# S7CAS-PLEIADES-CARTE-MERE_P01_FPGA-BANK3.net
KiCad netlist of a schematic drawn in Altium Designer
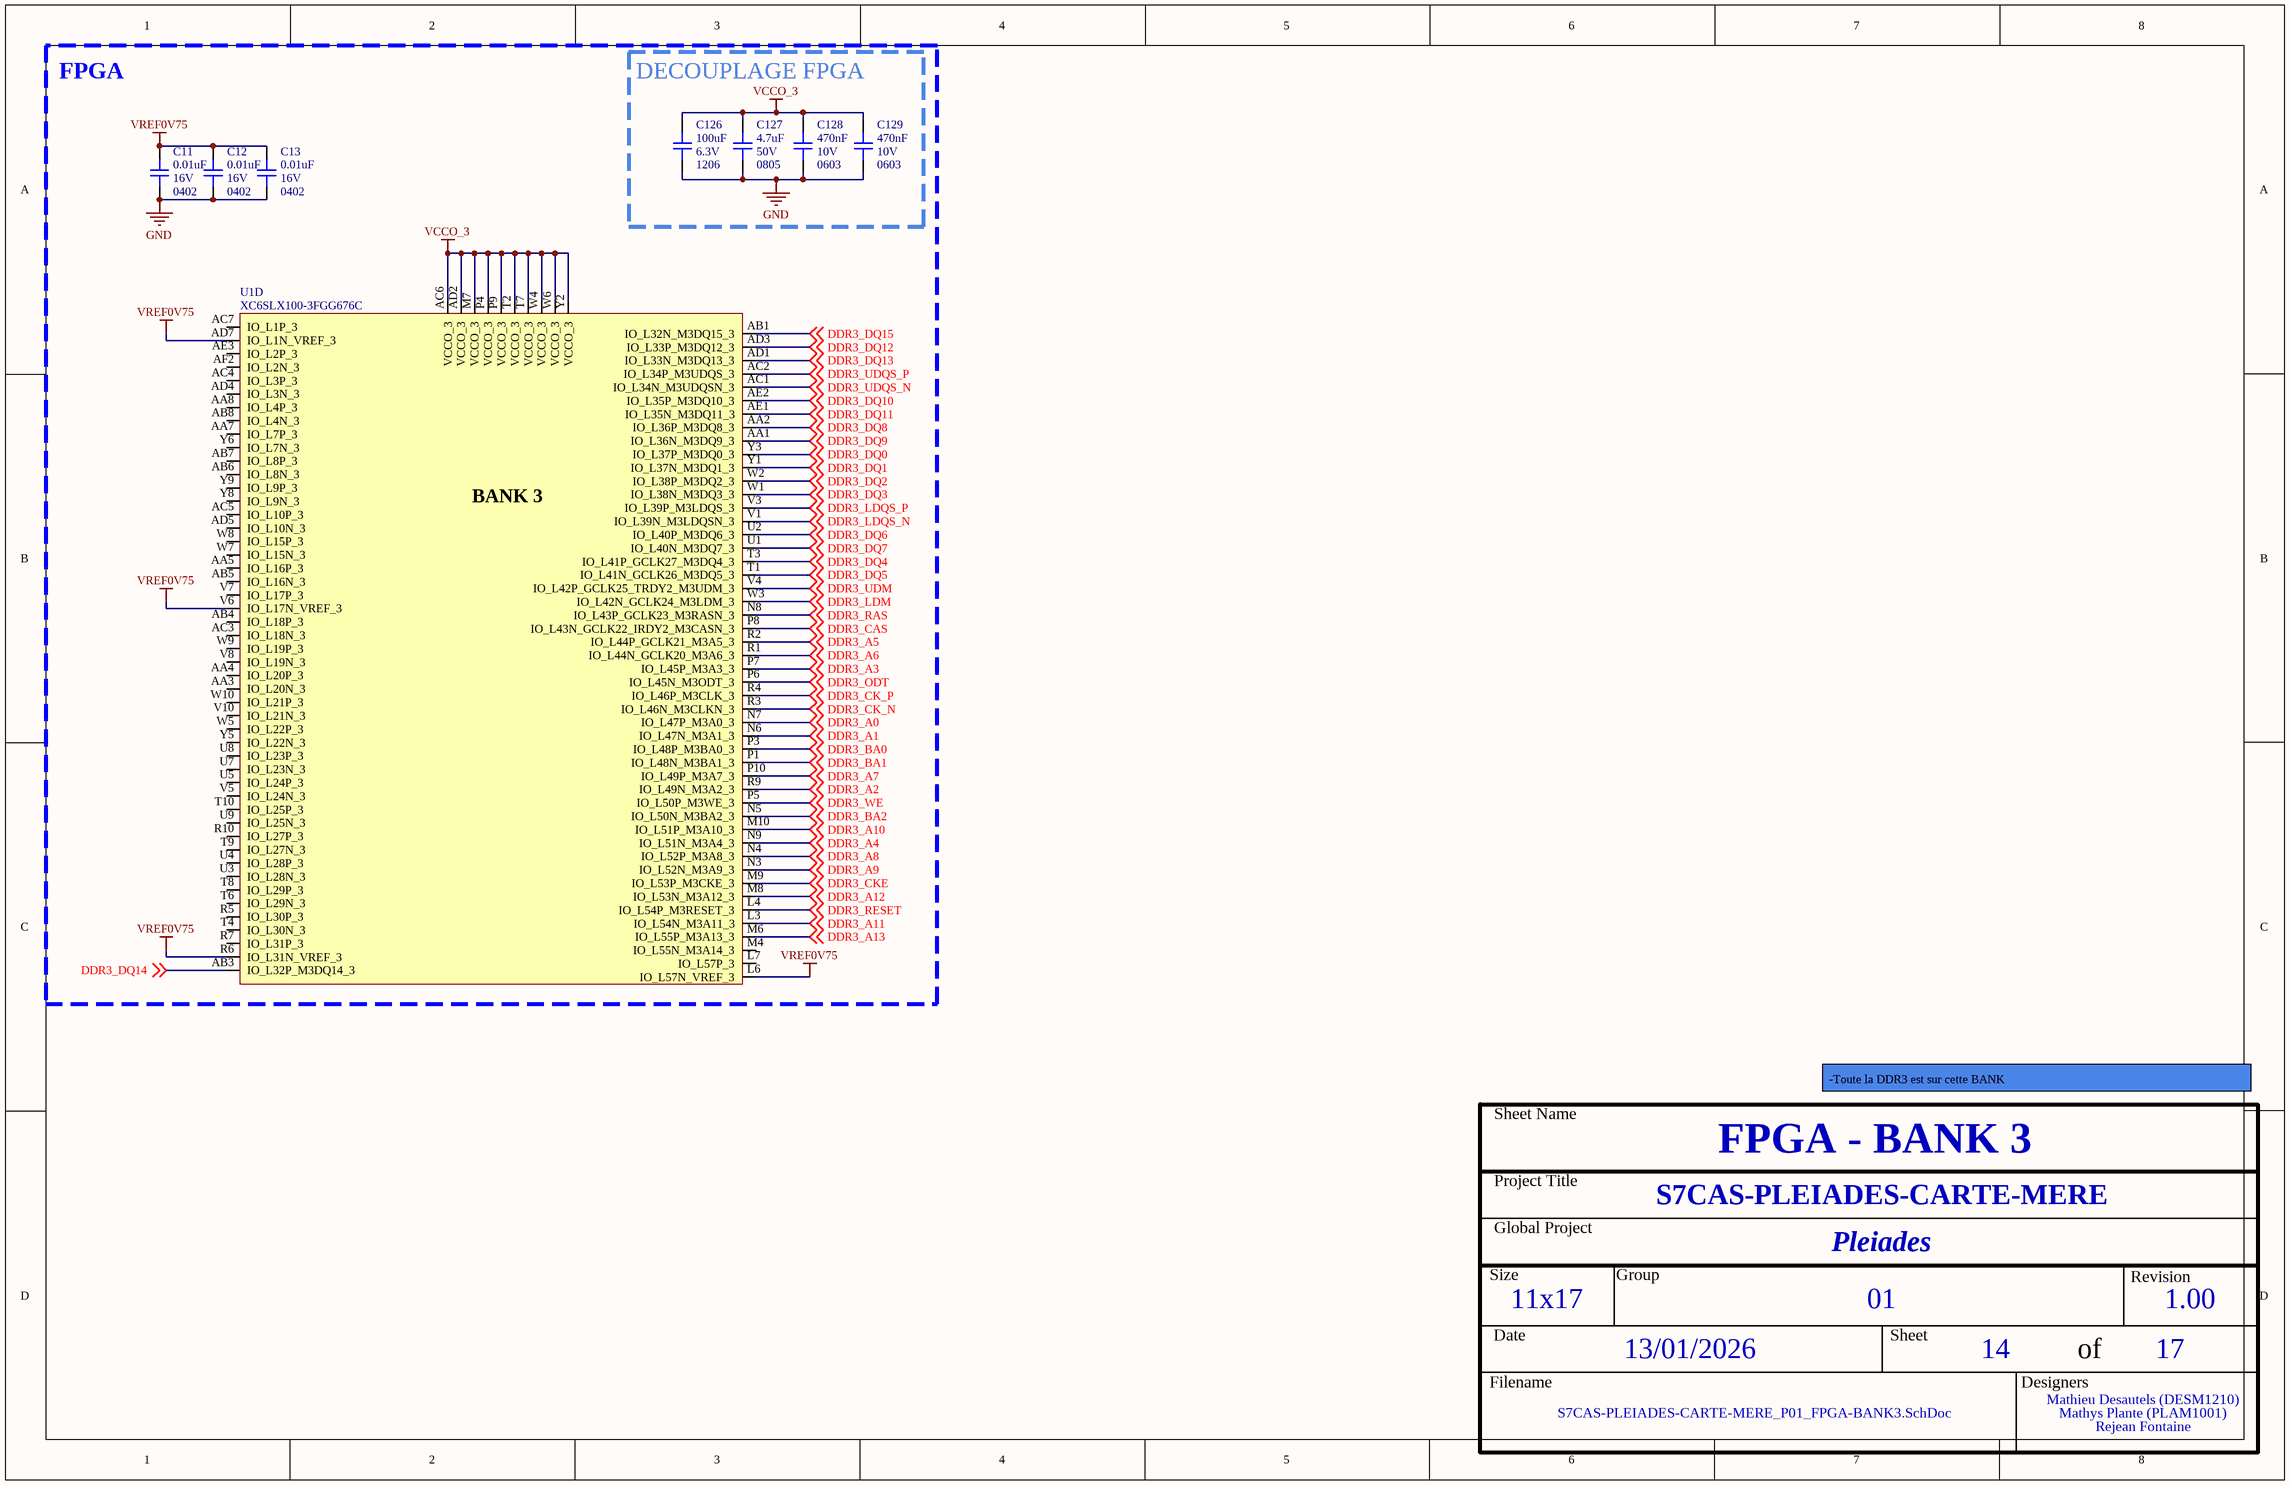
[diagram p0: S7CAS-PLEIADES-CARTE-MERE_P01_FPGA-BANK3.SchDoc]

(export (version "E")
  (design (tool "Eeschema 10.0.6"))
  (components
    (comp (ref "C11")
      (value "0.01uF")
      (footprint "CAP_0402")
      (description "10000 pF ±10% 16V Ceramic Capacitor X7R 0402 (1005 Metric)")
      (fields
        (field (name "MFG") "KEMET")
        (field (name "VOLTAGE") "16V")
        (field (name "PACKAGE") "0402")
        (field (name "MFG PART NUMBER") "C0402C103K4RACTU")
        (field (name "CREATEDBY") "Jonathan Bouchard")
      )
      (libsource (lib "s7cas_lib2023") (part "CAP - 0402"))
    )
    (comp (ref "C12")
      (value "0.01uF")
      (footprint "CAP_0402")
      (description "10000 pF ±10% 16V Ceramic Capacitor X7R 0402 (1005 Metric)")
      (fields
        (field (name "MFG") "KEMET")
        (field (name "VOLTAGE") "16V")
        (field (name "PACKAGE") "0402")
        (field (name "MFG PART NUMBER") "C0402C103K4RACTU")
        (field (name "CREATEDBY") "Jonathan Bouchard")
      )
      (libsource (lib "s7cas_lib2023") (part "CAP - 0402"))
    )
    (comp (ref "C13")
      (value "0.01uF")
      (footprint "CAP_0402")
      (description "10000 pF ±10% 16V Ceramic Capacitor X7R 0402 (1005 Metric)")
      (fields
        (field (name "MFG") "KEMET")
        (field (name "VOLTAGE") "16V")
        (field (name "PACKAGE") "0402")
        (field (name "MFG PART NUMBER") "C0402C103K4RACTU")
        (field (name "CREATEDBY") "Jonathan Bouchard")
      )
      (libsource (lib "s7cas_lib2023") (part "CAP - 0402"))
    )
    (comp (ref "C126")
      (value "100uF")
      (footprint "CAP_1206")
      (description "100 µF ±20% 6.3V Ceramic Capacitor X6T 1206 (3216 Metric)")
      (fields
        (field (name "MFG") "Murata Electronics")
        (field (name "MFG PART NUMBER") "GRM31CD80J107MEA8K")
        (field (name "VOLTAGE") "6.3V")
        (field (name "PACKAGE") "1206")
        (field (name "CREATEDBY") "Jonathan Bouchard")
      )
      (libsource (lib "s7cas_lib2023") (part "CAP - 1206"))
    )
    (comp (ref "C127")
      (value "4.7uF")
      (footprint "CAP_0805")
      (description "4.7 µF ±10% 50V Ceramic Capacitor X5R 0805 (2012 Metric)")
      (fields
        (field (name "MFG") "Murata Electronics")
        (field (name "MFG PART NUMBER") "GRT21BR61H475KE13L")
        (field (name "VOLTAGE") "50V")
        (field (name "PACKAGE") "0805")
        (field (name "CREATEDBY") "Jonathan Bouchard")
      )
      (libsource (lib "s7cas_lib2023") (part "CAP - 0805"))
    )
    (comp (ref "C128")
      (value "470nF")
      (footprint "CAP_0603")
      (description "CAP - 0603")
      (fields
        (field (name "MFG PART NUMBER") "C0603X474K8RAC")
        (field (name "VOLTAGE") "10V")
        (field (name "PACKAGE") "0603")
        (field (name "CREATEDBY") "Jonathan Bouchard")
      )
      (libsource (lib "s7cas_lib2023") (part "CAP - 0603"))
    )
    (comp (ref "C129")
      (value "470nF")
      (footprint "CAP_0603")
      (description "CAP - 0603")
      (fields
        (field (name "MFG PART NUMBER") "C0603X474K8RAC")
        (field (name "VOLTAGE") "10V")
        (field (name "PACKAGE") "0603")
        (field (name "CREATEDBY") "Jonathan Bouchard")
      )
      (libsource (lib "s7cas_lib2023") (part "CAP - 0603"))
    )
    (comp (ref "U1")
      (value "XC6SLX100-3FGG676C")
      (footprint "FPGA_XILINX_FGG676")
      (description "FPGA - XILINX SPARTAN 6 480 I/O - BGA-676")
      (fields
        (field (name "VOLTAGE") "1.14 V ~ 1.26 V")
        (field (name "MFG") "Xilinx")
        (field (name "CREATEDBY") "Jonathan Bouchard")
      )
      (libsource (lib "s7cas_lib2023") (part "FPGA_XC6SLX100-3FGG676C"))
    )
  )
  (nets
    (net (code "1") (name "DDR3_A0") (class "Default")
      (node (ref "U1") (pin "N7") (pinfunction "IO_L47P_M3A0_3_N7") (pintype "passive"))
    )
    (net (code "2") (name "DDR3_A1") (class "Default")
      (node (ref "U1") (pin "N6") (pinfunction "IO_L47N_M3A1_3_N6") (pintype "passive"))
    )
    (net (code "3") (name "DDR3_A2") (class "Default")
      (node (ref "U1") (pin "R9") (pinfunction "IO_L49N_M3A2_3_R9") (pintype "passive"))
    )
    (net (code "4") (name "DDR3_A3") (class "Default")
      (node (ref "U1") (pin "P7") (pinfunction "IO_L45P_M3A3_3_P7") (pintype "passive"))
    )
    (net (code "5") (name "DDR3_A4") (class "Default")
      (node (ref "U1") (pin "N9") (pinfunction "IO_L51N_M3A4_3_N9") (pintype "passive"))
    )
    (net (code "6") (name "DDR3_A5") (class "Default")
      (node (ref "U1") (pin "R2") (pinfunction "IO_L44P_GCLK21_M3A5_3_R2") (pintype "passive"))
    )
    (net (code "7") (name "DDR3_A6") (class "Default")
      (node (ref "U1") (pin "R1") (pinfunction "IO_L44N_GCLK20_M3A6_3_R1") (pintype "passive"))
    )
    (net (code "8") (name "DDR3_A7") (class "Default")
      (node (ref "U1") (pin "P10") (pinfunction "IO_L49P_M3A7_3_P10") (pintype "passive"))
    )
    (net (code "9") (name "DDR3_A8") (class "Default")
      (node (ref "U1") (pin "N4") (pinfunction "IO_L52P_M3A8_3_N4") (pintype "passive"))
    )
    (net (code "10") (name "DDR3_A9") (class "Default")
      (node (ref "U1") (pin "N3") (pinfunction "IO_L52N_M3A9_3_N3") (pintype "passive"))
    )
    (net (code "11") (name "DDR3_A10") (class "Default")
      (node (ref "U1") (pin "M10") (pinfunction "IO_L51P_M3A10_3_M10") (pintype "passive"))
    )
    (net (code "12") (name "DDR3_A11") (class "Default")
      (node (ref "U1") (pin "L3") (pinfunction "IO_L54N_M3A11_3_L3") (pintype "passive"))
    )
    (net (code "13") (name "DDR3_A12") (class "Default")
      (node (ref "U1") (pin "M8") (pinfunction "IO_L53N_M3A12_3_M8") (pintype "passive"))
    )
    (net (code "14") (name "DDR3_A13") (class "Default")
      (node (ref "U1") (pin "M6") (pinfunction "IO_L55P_M3A13_3_M6") (pintype "passive"))
    )
    (net (code "15") (name "DDR3_BA0") (class "Default")
      (node (ref "U1") (pin "P3") (pinfunction "IO_L48P_M3BA0_3_P3") (pintype "passive"))
    )
    (net (code "16") (name "DDR3_BA1") (class "Default")
      (node (ref "U1") (pin "P1") (pinfunction "IO_L48N_M3BA1_3_P1") (pintype "passive"))
    )
    (net (code "17") (name "DDR3_BA2") (class "Default")
      (node (ref "U1") (pin "N5") (pinfunction "IO_L50N_M3BA2_3_N5") (pintype "passive"))
    )
    (net (code "18") (name "DDR3_CAS") (class "Default")
      (node (ref "U1") (pin "P8") (pinfunction "IO_L43N_GCLK22_IRDY2_M3CASN_3_P8") (pintype "passive"))
    )
    (net (code "19") (name "DDR3_CKE") (class "Default")
      (node (ref "U1") (pin "M9") (pinfunction "IO_L53P_M3CKE_3_M9") (pintype "passive"))
    )
    (net (code "20") (name "DDR3_CK_N") (class "Default")
      (node (ref "U1") (pin "R3") (pinfunction "IO_L46N_M3CLKN_3_R3") (pintype "passive"))
    )
    (net (code "21") (name "DDR3_CK_P") (class "Default")
      (node (ref "U1") (pin "R4") (pinfunction "IO_L46P_M3CLK_3_R4") (pintype "passive"))
    )
    (net (code "22") (name "DDR3_DQ0") (class "Default")
      (node (ref "U1") (pin "Y3") (pinfunction "IO_L37P_M3DQ0_3_Y3") (pintype "passive"))
    )
    (net (code "23") (name "DDR3_DQ1") (class "Default")
      (node (ref "U1") (pin "Y1") (pinfunction "IO_L37N_M3DQ1_3_Y1") (pintype "passive"))
    )
    (net (code "24") (name "DDR3_DQ2") (class "Default")
      (node (ref "U1") (pin "W2") (pinfunction "IO_L38P_M3DQ2_3_W2") (pintype "passive"))
    )
    (net (code "25") (name "DDR3_DQ3") (class "Default")
      (node (ref "U1") (pin "W1") (pinfunction "IO_L38N_M3DQ3_3_W1") (pintype "passive"))
    )
    (net (code "26") (name "DDR3_DQ4") (class "Default")
      (node (ref "U1") (pin "T3") (pinfunction "IO_L41P_GCLK27_M3DQ4_3_T3") (pintype "passive"))
    )
    (net (code "27") (name "DDR3_DQ5") (class "Default")
      (node (ref "U1") (pin "T1") (pinfunction "IO_L41N_GCLK26_M3DQ5_3_T1") (pintype "passive"))
    )
    (net (code "28") (name "DDR3_DQ6") (class "Default")
      (node (ref "U1") (pin "U2") (pinfunction "IO_L40P_M3DQ6_3_U2") (pintype "passive"))
    )
    (net (code "29") (name "DDR3_DQ7") (class "Default")
      (node (ref "U1") (pin "U1") (pinfunction "IO_L40N_M3DQ7_3_U1") (pintype "passive"))
    )
    (net (code "30") (name "DDR3_DQ8") (class "Default")
      (node (ref "U1") (pin "AA2") (pinfunction "IO_L36P_M3DQ8_3_AA2") (pintype "passive"))
    )
    (net (code "31") (name "DDR3_DQ9") (class "Default")
      (node (ref "U1") (pin "AA1") (pinfunction "IO_L36N_M3DQ9_3_AA1") (pintype "passive"))
    )
    (net (code "32") (name "DDR3_DQ10") (class "Default")
      (node (ref "U1") (pin "AE2") (pinfunction "IO_L35P_M3DQ10_3_AE2") (pintype "passive"))
    )
    (net (code "33") (name "DDR3_DQ11") (class "Default")
      (node (ref "U1") (pin "AE1") (pinfunction "IO_L35N_M3DQ11_3_AE1") (pintype "passive"))
    )
    (net (code "34") (name "DDR3_DQ12") (class "Default")
      (node (ref "U1") (pin "AD3") (pinfunction "IO_L33P_M3DQ12_3_AD3") (pintype "passive"))
    )
    (net (code "35") (name "DDR3_DQ13") (class "Default")
      (node (ref "U1") (pin "AD1") (pinfunction "IO_L33N_M3DQ13_3_AD1") (pintype "passive"))
    )
    (net (code "36") (name "DDR3_DQ14") (class "Default")
      (node (ref "U1") (pin "AB3") (pinfunction "IO_L32P_M3DQ14_3_AB3") (pintype "passive"))
    )
    (net (code "37") (name "DDR3_DQ15") (class "Default")
      (node (ref "U1") (pin "AB1") (pinfunction "IO_L32N_M3DQ15_3_AB1") (pintype "passive"))
    )
    (net (code "38") (name "DDR3_LDM") (class "Default")
      (node (ref "U1") (pin "W3") (pinfunction "IO_L42N_GCLK24_M3LDM_3_W3") (pintype "passive"))
    )
    (net (code "39") (name "DDR3_LDQS_N") (class "Default")
      (node (ref "U1") (pin "V1") (pinfunction "IO_L39N_M3LDQSN_3_V1") (pintype "passive"))
    )
    (net (code "40") (name "DDR3_LDQS_P") (class "Default")
      (node (ref "U1") (pin "V3") (pinfunction "IO_L39P_M3LDQS_3_V3") (pintype "passive"))
    )
    (net (code "41") (name "DDR3_ODT") (class "Default")
      (node (ref "U1") (pin "P6") (pinfunction "IO_L45N_M3ODT_3_P6") (pintype "passive"))
    )
    (net (code "42") (name "DDR3_RAS") (class "Default")
      (node (ref "U1") (pin "N8") (pinfunction "IO_L43P_GCLK23_M3RASN_3_N8") (pintype "passive"))
    )
    (net (code "43") (name "DDR3_RESET") (class "Default")
      (node (ref "U1") (pin "L4") (pinfunction "IO_L54P_M3RESET_3_L4") (pintype "passive"))
    )
    (net (code "44") (name "DDR3_UDM") (class "Default")
      (node (ref "U1") (pin "V4") (pinfunction "IO_L42P_GCLK25_TRDY2_M3UDM_3_V4") (pintype "passive"))
    )
    (net (code "45") (name "DDR3_UDQS_N") (class "Default")
      (node (ref "U1") (pin "AC1") (pinfunction "IO_L34N_M3UDQSN_3_AC1") (pintype "passive"))
    )
    (net (code "46") (name "DDR3_UDQS_P") (class "Default")
      (node (ref "U1") (pin "AC2") (pinfunction "IO_L34P_M3UDQS_3_AC2") (pintype "passive"))
    )
    (net (code "47") (name "DDR3_WE") (class "Default")
      (node (ref "U1") (pin "P5") (pinfunction "IO_L50P_M3WE_3_P5") (pintype "passive"))
    )
    (net (code "48") (name "GND") (class "Default")
      (node (ref "C11") (pin "1") (pinfunction "1_1") (pintype "passive"))
      (node (ref "C12") (pin "1") (pinfunction "1_1") (pintype "passive"))
      (node (ref "C126") (pin "1") (pinfunction "1_1") (pintype "passive"))
      (node (ref "C127") (pin "1") (pinfunction "1_1") (pintype "passive"))
      (node (ref "C128") (pin "1") (pinfunction "1_1") (pintype "passive"))
      (node (ref "C129") (pin "1") (pinfunction "1_1") (pintype "passive"))
      (node (ref "C13") (pin "1") (pinfunction "1_1") (pintype "passive"))
    )
    (net (code "49") (name "VCCO_3") (class "Default")
      (node (ref "C126") (pin "2") (pinfunction "2_2") (pintype "passive"))
      (node (ref "C127") (pin "2") (pinfunction "2_2") (pintype "passive"))
      (node (ref "C128") (pin "2") (pinfunction "2_2") (pintype "passive"))
      (node (ref "C129") (pin "2") (pinfunction "2_2") (pintype "passive"))
      (node (ref "U1") (pin "AC6") (pinfunction "VCCO_3_AC6") (pintype "passive"))
      (node (ref "U1") (pin "AD2") (pinfunction "VCCO_3_AD2") (pintype "passive"))
      (node (ref "U1") (pin "M7") (pinfunction "VCCO_3_M7") (pintype "passive"))
      (node (ref "U1") (pin "P4") (pinfunction "VCCO_3_P4") (pintype "passive"))
      (node (ref "U1") (pin "P9") (pinfunction "VCCO_3_P9") (pintype "passive"))
      (node (ref "U1") (pin "T2") (pinfunction "VCCO_3_T2") (pintype "passive"))
      (node (ref "U1") (pin "T7") (pinfunction "VCCO_3_T7") (pintype "passive"))
      (node (ref "U1") (pin "W4") (pinfunction "VCCO_3_W4") (pintype "passive"))
      (node (ref "U1") (pin "W6") (pinfunction "VCCO_3_W6") (pintype "passive"))
      (node (ref "U1") (pin "Y2") (pinfunction "VCCO_3_Y2") (pintype "passive"))
    )
    (net (code "50") (name "VREF0V75") (class "Default")
      (node (ref "C11") (pin "2") (pinfunction "2_2") (pintype "passive"))
      (node (ref "C12") (pin "2") (pinfunction "2_2") (pintype "passive"))
      (node (ref "C13") (pin "2") (pinfunction "2_2") (pintype "passive"))
      (node (ref "U1") (pin "AD7") (pinfunction "IO_L1N_VREF_3_AD7") (pintype "passive"))
      (node (ref "U1") (pin "L6") (pinfunction "IO_L57N_VREF_3_L6") (pintype "passive"))
      (node (ref "U1") (pin "R6") (pinfunction "IO_L31N_VREF_3_R6") (pintype "passive"))
      (node (ref "U1") (pin "V6") (pinfunction "IO_L17N_VREF_3_V6") (pintype "passive"))
    )
    (net (code "51") (name "unconnected-(U1D-IO_L1P_3-PadAC7)") (class "Default")
      (node (ref "U1") (pin "AC7") (pinfunction "IO_L1P_3_AC7") (pintype "passive"))
    )
    (net (code "52") (name "unconnected-(U1D-IO_L2N_3-PadAF2)") (class "Default")
      (node (ref "U1") (pin "AF2") (pinfunction "IO_L2N_3_AF2") (pintype "passive"))
    )
    (net (code "53") (name "unconnected-(U1D-IO_L2P_3-PadAE3)") (class "Default")
      (node (ref "U1") (pin "AE3") (pinfunction "IO_L2P_3_AE3") (pintype "passive"))
    )
    (net (code "54") (name "unconnected-(U1D-IO_L3N_3-PadAD4)") (class "Default")
      (node (ref "U1") (pin "AD4") (pinfunction "IO_L3N_3_AD4") (pintype "passive"))
    )
    (net (code "55") (name "unconnected-(U1D-IO_L3P_3-PadAC4)") (class "Default")
      (node (ref "U1") (pin "AC4") (pinfunction "IO_L3P_3_AC4") (pintype "passive"))
    )
    (net (code "56") (name "unconnected-(U1D-IO_L4N_3-PadAB8)") (class "Default")
      (node (ref "U1") (pin "AB8") (pinfunction "IO_L4N_3_AB8") (pintype "passive"))
    )
    (net (code "57") (name "unconnected-(U1D-IO_L4P_3-PadAA8)") (class "Default")
      (node (ref "U1") (pin "AA8") (pinfunction "IO_L4P_3_AA8") (pintype "passive"))
    )
    (net (code "58") (name "unconnected-(U1D-IO_L7N_3-PadY6)") (class "Default")
      (node (ref "U1") (pin "Y6") (pinfunction "IO_L7N_3_Y6") (pintype "passive"))
    )
    (net (code "59") (name "unconnected-(U1D-IO_L7P_3-PadAA7)") (class "Default")
      (node (ref "U1") (pin "AA7") (pinfunction "IO_L7P_3_AA7") (pintype "passive"))
    )
    (net (code "60") (name "unconnected-(U1D-IO_L8N_3-PadAB6)") (class "Default")
      (node (ref "U1") (pin "AB6") (pinfunction "IO_L8N_3_AB6") (pintype "passive"))
    )
    (net (code "61") (name "unconnected-(U1D-IO_L8P_3-PadAB7)") (class "Default")
      (node (ref "U1") (pin "AB7") (pinfunction "IO_L8P_3_AB7") (pintype "passive"))
    )
    (net (code "62") (name "unconnected-(U1D-IO_L9N_3-PadY8)") (class "Default")
      (node (ref "U1") (pin "Y8") (pinfunction "IO_L9N_3_Y8") (pintype "passive"))
    )
    (net (code "63") (name "unconnected-(U1D-IO_L9P_3-PadY9)") (class "Default")
      (node (ref "U1") (pin "Y9") (pinfunction "IO_L9P_3_Y9") (pintype "passive"))
    )
    (net (code "64") (name "unconnected-(U1D-IO_L10N_3-PadAD5)") (class "Default")
      (node (ref "U1") (pin "AD5") (pinfunction "IO_L10N_3_AD5") (pintype "passive"))
    )
    (net (code "65") (name "unconnected-(U1D-IO_L10P_3-PadAC5)") (class "Default")
      (node (ref "U1") (pin "AC5") (pinfunction "IO_L10P_3_AC5") (pintype "passive"))
    )
    (net (code "66") (name "unconnected-(U1D-IO_L15N_3-PadW7)") (class "Default")
      (node (ref "U1") (pin "W7") (pinfunction "IO_L15N_3_W7") (pintype "passive"))
    )
    (net (code "67") (name "unconnected-(U1D-IO_L15P_3-PadW8)") (class "Default")
      (node (ref "U1") (pin "W8") (pinfunction "IO_L15P_3_W8") (pintype "passive"))
    )
    (net (code "68") (name "unconnected-(U1D-IO_L16N_3-PadAB5)") (class "Default")
      (node (ref "U1") (pin "AB5") (pinfunction "IO_L16N_3_AB5") (pintype "passive"))
    )
    (net (code "69") (name "unconnected-(U1D-IO_L16P_3-PadAA5)") (class "Default")
      (node (ref "U1") (pin "AA5") (pinfunction "IO_L16P_3_AA5") (pintype "passive"))
    )
    (net (code "70") (name "unconnected-(U1D-IO_L17P_3-PadV7)") (class "Default")
      (node (ref "U1") (pin "V7") (pinfunction "IO_L17P_3_V7") (pintype "passive"))
    )
    (net (code "71") (name "unconnected-(U1D-IO_L18N_3-PadAC3)") (class "Default")
      (node (ref "U1") (pin "AC3") (pinfunction "IO_L18N_3_AC3") (pintype "passive"))
    )
    (net (code "72") (name "unconnected-(U1D-IO_L18P_3-PadAB4)") (class "Default")
      (node (ref "U1") (pin "AB4") (pinfunction "IO_L18P_3_AB4") (pintype "passive"))
    )
    (net (code "73") (name "unconnected-(U1D-IO_L19N_3-PadV8)") (class "Default")
      (node (ref "U1") (pin "V8") (pinfunction "IO_L19N_3_V8") (pintype "passive"))
    )
    (net (code "74") (name "unconnected-(U1D-IO_L19P_3-PadW9)") (class "Default")
      (node (ref "U1") (pin "W9") (pinfunction "IO_L19P_3_W9") (pintype "passive"))
    )
    (net (code "75") (name "unconnected-(U1D-IO_L20N_3-PadAA3)") (class "Default")
      (node (ref "U1") (pin "AA3") (pinfunction "IO_L20N_3_AA3") (pintype "passive"))
    )
    (net (code "76") (name "unconnected-(U1D-IO_L20P_3-PadAA4)") (class "Default")
      (node (ref "U1") (pin "AA4") (pinfunction "IO_L20P_3_AA4") (pintype "passive"))
    )
    (net (code "77") (name "unconnected-(U1D-IO_L21N_3-PadV10)") (class "Default")
      (node (ref "U1") (pin "V10") (pinfunction "IO_L21N_3_V10") (pintype "passive"))
    )
    (net (code "78") (name "unconnected-(U1D-IO_L21P_3-PadW10)") (class "Default")
      (node (ref "U1") (pin "W10") (pinfunction "IO_L21P_3_W10") (pintype "passive"))
    )
    (net (code "79") (name "unconnected-(U1D-IO_L22N_3-PadY5)") (class "Default")
      (node (ref "U1") (pin "Y5") (pinfunction "IO_L22N_3_Y5") (pintype "passive"))
    )
    (net (code "80") (name "unconnected-(U1D-IO_L22P_3-PadW5)") (class "Default")
      (node (ref "U1") (pin "W5") (pinfunction "IO_L22P_3_W5") (pintype "passive"))
    )
    (net (code "81") (name "unconnected-(U1D-IO_L23N_3-PadU7)") (class "Default")
      (node (ref "U1") (pin "U7") (pinfunction "IO_L23N_3_U7") (pintype "passive"))
    )
    (net (code "82") (name "unconnected-(U1D-IO_L23P_3-PadU8)") (class "Default")
      (node (ref "U1") (pin "U8") (pinfunction "IO_L23P_3_U8") (pintype "passive"))
    )
    (net (code "83") (name "unconnected-(U1D-IO_L24N_3-PadV5)") (class "Default")
      (node (ref "U1") (pin "V5") (pinfunction "IO_L24N_3_V5") (pintype "passive"))
    )
    (net (code "84") (name "unconnected-(U1D-IO_L24P_3-PadU5)") (class "Default")
      (node (ref "U1") (pin "U5") (pinfunction "IO_L24P_3_U5") (pintype "passive"))
    )
    (net (code "85") (name "unconnected-(U1D-IO_L25N_3-PadU9)") (class "Default")
      (node (ref "U1") (pin "U9") (pinfunction "IO_L25N_3_U9") (pintype "passive"))
    )
    (net (code "86") (name "unconnected-(U1D-IO_L25P_3-PadT10)") (class "Default")
      (node (ref "U1") (pin "T10") (pinfunction "IO_L25P_3_T10") (pintype "passive"))
    )
    (net (code "87") (name "unconnected-(U1D-IO_L27N_3-PadT9)") (class "Default")
      (node (ref "U1") (pin "T9") (pinfunction "IO_L27N_3_T9") (pintype "passive"))
    )
    (net (code "88") (name "unconnected-(U1D-IO_L27P_3-PadR10)") (class "Default")
      (node (ref "U1") (pin "R10") (pinfunction "IO_L27P_3_R10") (pintype "passive"))
    )
    (net (code "89") (name "unconnected-(U1D-IO_L28N_3-PadU3)") (class "Default")
      (node (ref "U1") (pin "U3") (pinfunction "IO_L28N_3_U3") (pintype "passive"))
    )
    (net (code "90") (name "unconnected-(U1D-IO_L28P_3-PadU4)") (class "Default")
      (node (ref "U1") (pin "U4") (pinfunction "IO_L28P_3_U4") (pintype "passive"))
    )
    (net (code "91") (name "unconnected-(U1D-IO_L29N_3-PadT6)") (class "Default")
      (node (ref "U1") (pin "T6") (pinfunction "IO_L29N_3_T6") (pintype "passive"))
    )
    (net (code "92") (name "unconnected-(U1D-IO_L29P_3-PadT8)") (class "Default")
      (node (ref "U1") (pin "T8") (pinfunction "IO_L29P_3_T8") (pintype "passive"))
    )
    (net (code "93") (name "unconnected-(U1D-IO_L30N_3-PadT4)") (class "Default")
      (node (ref "U1") (pin "T4") (pinfunction "IO_L30N_3_T4") (pintype "passive"))
    )
    (net (code "94") (name "unconnected-(U1D-IO_L30P_3-PadR5)") (class "Default")
      (node (ref "U1") (pin "R5") (pinfunction "IO_L30P_3_R5") (pintype "passive"))
    )
    (net (code "95") (name "unconnected-(U1D-IO_L31P_3-PadR7)") (class "Default")
      (node (ref "U1") (pin "R7") (pinfunction "IO_L31P_3_R7") (pintype "passive"))
    )
    (net (code "96") (name "unconnected-(U1D-IO_L55N_M3A14_3-PadM4)") (class "Default")
      (node (ref "U1") (pin "M4") (pinfunction "IO_L55N_M3A14_3_M4") (pintype "passive"))
    )
    (net (code "97") (name "unconnected-(U1D-IO_L57P_3-PadL7)") (class "Default")
      (node (ref "U1") (pin "L7") (pinfunction "IO_L57P_3_L7") (pintype "passive"))
    )
  )
)
